# RFG-controller.net
KiCad netlist of a schematic drawn in EAGLE
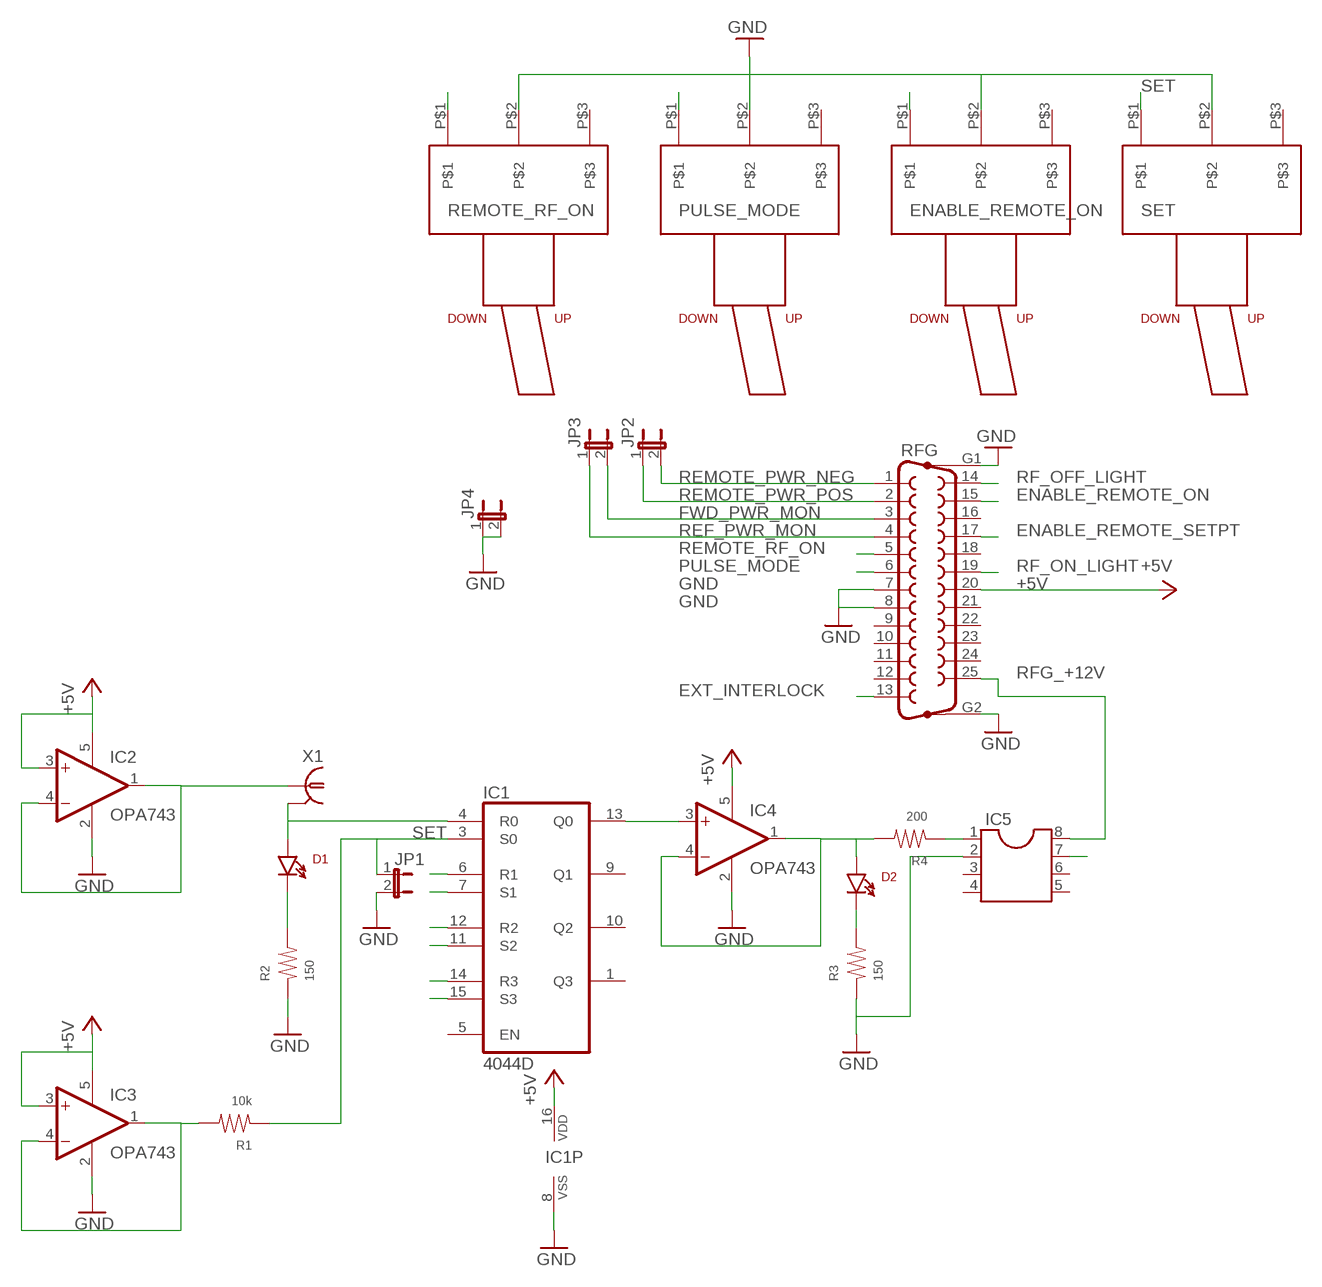
[diagram p0: schematic, sheet 1]

(export (version "E")
  (design (tool "Eeschema 10.0.6"))
  (components
    (comp (ref "D1")
      (value "LED")
      (footprint "eagle-import:LTL-533-11")
      (libsource (lib "eagle-import") (part "LED"))
    )
    (comp (ref "D2")
      (value "LED")
      (footprint "eagle-import:LTL-533-11")
      (libsource (lib "eagle-import") (part "LED"))
    )
    (comp (ref "ENABLE_REMOTE_ON")
      (value "SPDT-TOGGLE")
      (footprint "eagle-import:7101MD9AV2BE")
      (libsource (lib "eagle-import") (part "SPDT-TOGGLE"))
    )
    (comp (ref "IC1")
      (value "4044D")
      (footprint "eagle-import:SO16")
      (libsource (lib "eagle-import") (part "4044D"))
    )
    (comp (ref "IC2")
      (value "OPA743")
      (footprint "eagle-import:SOT23-5")
      (fields (field (name "PARTNO") "OPA743NA/3KCT-ND"))
      (libsource (lib "eagle-import") (part "OPA743"))
    )
    (comp (ref "IC3")
      (value "OPA743")
      (footprint "eagle-import:SOT23-5")
      (fields (field (name "PARTNO") "OPA743NA/3KCT-ND"))
      (libsource (lib "eagle-import") (part "OPA743"))
    )
    (comp (ref "IC4")
      (value "OPA743")
      (footprint "eagle-import:SOT23-5")
      (fields (field (name "PARTNO") "OPA743NA/3KCT-ND"))
      (libsource (lib "eagle-import") (part "OPA743"))
    )
    (comp (ref "IC5")
      (value "DIL8")
      (footprint "eagle-import:DIL08")
      (libsource (lib "eagle-import") (part "DIL8"))
    )
    (comp (ref "JP1")
      (value "JP1E")
      (footprint "eagle-import:JP1")
      (libsource (lib "eagle-import") (part "JP1E"))
    )
    (comp (ref "JP2")
      (value "JP1E")
      (footprint "eagle-import:JP1")
      (libsource (lib "eagle-import") (part "JP1E"))
    )
    (comp (ref "JP3")
      (value "JP1E")
      (footprint "eagle-import:JP1")
      (libsource (lib "eagle-import") (part "JP1E"))
    )
    (comp (ref "JP4")
      (value "JP1E")
      (footprint "eagle-import:JP1")
      (libsource (lib "eagle-import") (part "JP1E"))
    )
    (comp (ref "PULSE_MODE")
      (value "SPDT-TOGGLE")
      (footprint "eagle-import:7101MD9AV2BE")
      (libsource (lib "eagle-import") (part "SPDT-TOGGLE"))
    )
    (comp (ref "R1")
      (value "10k")
      (footprint "eagle-import:0603")
      (libsource (lib "eagle-import") (part "RES0603"))
    )
    (comp (ref "R2")
      (value "150")
      (footprint "eagle-import:0603")
      (libsource (lib "eagle-import") (part "RES0603"))
    )
    (comp (ref "R3")
      (value "150")
      (footprint "eagle-import:0603")
      (libsource (lib "eagle-import") (part "RES0603"))
    )
    (comp (ref "R4")
      (value "200")
      (footprint "eagle-import:0603")
      (libsource (lib "eagle-import") (part "RES0603"))
    )
    (comp (ref "REMOTE_ON")
      (value "SPDT-TOGGLE")
      (footprint "eagle-import:7101MD9AV2BE")
      (libsource (lib "eagle-import") (part "SPDT-TOGGLE"))
    )
    (comp (ref "RFG")
      (value "F25HP")
      (footprint "eagle-import:F25HP")
      (libsource (lib "eagle-import") (part "F25HP"))
    )
    (comp (ref "SET")
      (value "SPDT-TOGGLE")
      (footprint "eagle-import:7101MD9AV2BE")
      (libsource (lib "eagle-import") (part "SPDT-TOGGLE"))
    )
    (comp (ref "X1")
      (value "BNC-H")
      (footprint "eagle-import:BNC90")
      (libsource (lib "eagle-import") (part "BNC-H"))
    )
  )
  (nets
    (net (code "1") (name "+5V") (class "Default")
      (node (ref "IC1") (pin "16") (pinfunction "VDD_16") (pintype "power_in"))
      (node (ref "IC2") (pin "3") (pinfunction "+IN_3") (pintype "input"))
      (node (ref "IC2") (pin "5") (pinfunction "V+_5") (pintype "power_in"))
      (node (ref "IC3") (pin "3") (pinfunction "+IN_3") (pintype "input"))
      (node (ref "IC3") (pin "5") (pinfunction "V+_5") (pintype "power_in"))
      (node (ref "IC4") (pin "5") (pinfunction "V+_5") (pintype "power_in"))
      (node (ref "RFG") (pin "20") (pinfunction "20_20") (pintype "passive"))
    )
    (net (code "2") (name "/ENABLE_REMOTE_ON") (class "Default")
      (node (ref "ENABLE_REMOTE_ON") (pin "P$1") (pinfunction "P$1_P$1") (pintype "bidirectional"))
      (node (ref "RFG") (pin "15") (pinfunction "15_15") (pintype "passive"))
    )
    (net (code "3") (name "/ENABLE_REMOTE_SETPT") (class "Default")
      (node (ref "RFG") (pin "17") (pinfunction "17_17") (pintype "passive"))
    )
    (net (code "4") (name "/EXT_INTERLOCK") (class "Default")
      (node (ref "IC5") (pin "7") (pinfunction "7_7") (pintype "passive"))
      (node (ref "RFG") (pin "13") (pinfunction "13_13") (pintype "passive"))
    )
    (net (code "5") (name "/FWD_PWR_MON") (class "Default")
      (node (ref "JP3") (pin "2") (pinfunction "2_2") (pintype "passive"))
      (node (ref "RFG") (pin "3") (pinfunction "3_3") (pintype "passive"))
    )
    (net (code "6") (name "/PULSE_MODE") (class "Default")
      (node (ref "PULSE_MODE") (pin "P$1") (pinfunction "P$1_P$1") (pintype "bidirectional"))
      (node (ref "RFG") (pin "6") (pinfunction "6_6") (pintype "passive"))
    )
    (net (code "7") (name "/REF_PWR_MON") (class "Default")
      (node (ref "JP3") (pin "1") (pinfunction "1_1") (pintype "passive"))
      (node (ref "RFG") (pin "4") (pinfunction "4_4") (pintype "passive"))
    )
    (net (code "8") (name "/REMOTE_PWR_NEG") (class "Default")
      (node (ref "JP2") (pin "2") (pinfunction "2_2") (pintype "passive"))
      (node (ref "RFG") (pin "1") (pinfunction "1_1") (pintype "passive"))
    )
    (net (code "9") (name "/REMOTE_PWR_POS") (class "Default")
      (node (ref "JP2") (pin "1") (pinfunction "1_1") (pintype "passive"))
      (node (ref "RFG") (pin "2") (pinfunction "2_2") (pintype "passive"))
    )
    (net (code "10") (name "/REMOTE_RF_ON") (class "Default")
      (node (ref "REMOTE_ON") (pin "P$1") (pinfunction "P$1_P$1") (pintype "bidirectional"))
      (node (ref "RFG") (pin "5") (pinfunction "5_5") (pintype "passive"))
    )
    (net (code "11") (name "/RFG_+12V") (class "Default")
      (node (ref "IC5") (pin "8") (pinfunction "8_8") (pintype "passive"))
      (node (ref "RFG") (pin "25") (pinfunction "25_25") (pintype "passive"))
    )
    (net (code "12") (name "/RF_OFF_LIGHT") (class "Default")
      (node (ref "RFG") (pin "14") (pinfunction "14_14") (pintype "passive"))
    )
    (net (code "13") (name "/RF_ON_LIGHT") (class "Default")
      (node (ref "RFG") (pin "19") (pinfunction "19_19") (pintype "passive"))
    )
    (net (code "14") (name "/SET") (class "Default")
      (node (ref "IC1") (pin "3") (pinfunction "S0_3") (pintype "input"))
      (node (ref "JP1") (pin "1") (pinfunction "1_1") (pintype "passive"))
      (node (ref "R1") (pin "1") (pinfunction "P$1_1") (pintype "passive"))
      (node (ref "SET") (pin "P$1") (pinfunction "P$1_P$1") (pintype "bidirectional"))
    )
    (net (code "15") (name "GND") (class "Default")
      (node (ref "ENABLE_REMOTE_ON") (pin "P$2") (pinfunction "P$2_P$2") (pintype "bidirectional"))
      (node (ref "IC1") (pin "11") (pinfunction "S2_11") (pintype "input"))
      (node (ref "IC1") (pin "12") (pinfunction "R2_12") (pintype "input"))
      (node (ref "IC1") (pin "14") (pinfunction "R3_14") (pintype "input"))
      (node (ref "IC1") (pin "15") (pinfunction "S3_15") (pintype "input"))
      (node (ref "IC1") (pin "6") (pinfunction "R1_6") (pintype "input"))
      (node (ref "IC1") (pin "7") (pinfunction "S1_7") (pintype "input"))
      (node (ref "IC1") (pin "8") (pinfunction "VSS_8") (pintype "power_in"))
      (node (ref "IC2") (pin "2") (pinfunction "V-_2") (pintype "power_in"))
      (node (ref "IC3") (pin "2") (pinfunction "V-_2") (pintype "power_in"))
      (node (ref "IC4") (pin "2") (pinfunction "V-_2") (pintype "power_in"))
      (node (ref "IC5") (pin "2") (pinfunction "2_2") (pintype "passive"))
      (node (ref "JP1") (pin "2") (pinfunction "2_2") (pintype "passive"))
      (node (ref "JP4") (pin "1") (pinfunction "1_1") (pintype "passive"))
      (node (ref "JP4") (pin "2") (pinfunction "2_2") (pintype "passive"))
      (node (ref "PULSE_MODE") (pin "P$2") (pinfunction "P$2_P$2") (pintype "bidirectional"))
      (node (ref "R2") (pin "1") (pinfunction "P$1_1") (pintype "passive"))
      (node (ref "R3") (pin "1") (pinfunction "P$1_1") (pintype "passive"))
      (node (ref "REMOTE_ON") (pin "P$2") (pinfunction "P$2_P$2") (pintype "bidirectional"))
      (node (ref "RFG") (pin "7") (pinfunction "7_7") (pintype "passive"))
      (node (ref "RFG") (pin "8") (pinfunction "8_8") (pintype "passive"))
      (node (ref "RFG") (pin "G1") (pinfunction "G1_G1") (pintype "passive"))
      (node (ref "RFG") (pin "G2") (pinfunction "G2_G2") (pintype "passive"))
      (node (ref "SET") (pin "P$2") (pinfunction "P$2_P$2") (pintype "bidirectional"))
    )
    (net (code "16") (name "Net-(IC1A-Q0)") (class "Default")
      (node (ref "IC1") (pin "13") (pinfunction "Q0_13") (pintype "output"))
      (node (ref "IC4") (pin "3") (pinfunction "+IN_3") (pintype "input"))
    )
    (net (code "17") (name "Net-(IC1A-R0)") (class "Default")
      (node (ref "D1") (pin "A") (pinfunction "A_A") (pintype "bidirectional"))
      (node (ref "IC1") (pin "4") (pinfunction "R0_4") (pintype "input"))
      (node (ref "X1") (pin "2") (pinfunction "2_2") (pintype "passive"))
    )
    (net (code "18") (name "Net-(IC2--IN)") (class "Default")
      (node (ref "IC2") (pin "1") (pinfunction "OUT_1") (pintype "output"))
      (node (ref "IC2") (pin "4") (pinfunction "-IN_4") (pintype "input"))
      (node (ref "X1") (pin "1") (pinfunction "1_1") (pintype "passive"))
    )
    (net (code "19") (name "Net-(IC3--IN)") (class "Default")
      (node (ref "IC3") (pin "1") (pinfunction "OUT_1") (pintype "output"))
      (node (ref "IC3") (pin "4") (pinfunction "-IN_4") (pintype "input"))
      (node (ref "R1") (pin "2") (pinfunction "P$2_2") (pintype "passive"))
    )
    (net (code "20") (name "Net-(IC4--IN)") (class "Default")
      (node (ref "D2") (pin "A") (pinfunction "A_A") (pintype "bidirectional"))
      (node (ref "IC4") (pin "1") (pinfunction "OUT_1") (pintype "output"))
      (node (ref "IC4") (pin "4") (pinfunction "-IN_4") (pintype "input"))
      (node (ref "R4") (pin "2") (pinfunction "P$2_2") (pintype "passive"))
    )
    (net (code "21") (name "Net-(R2-P$2)") (class "Default")
      (node (ref "D1") (pin "C") (pinfunction "C_C") (pintype "bidirectional"))
      (node (ref "R2") (pin "2") (pinfunction "P$2_2") (pintype "passive"))
    )
    (net (code "22") (name "Net-(R3-P$2)") (class "Default")
      (node (ref "D2") (pin "C") (pinfunction "C_C") (pintype "bidirectional"))
      (node (ref "R3") (pin "2") (pinfunction "P$2_2") (pintype "passive"))
    )
    (net (code "23") (name "Net-(R4-P$1)") (class "Default")
      (node (ref "IC5") (pin "1") (pinfunction "1_1") (pintype "passive"))
      (node (ref "R4") (pin "1") (pinfunction "P$1_1") (pintype "passive"))
    )
    (net (code "24") (name "unconnected-(ENABLE_REMOTE_ON-PadP$3)") (class "Default")
      (node (ref "ENABLE_REMOTE_ON") (pin "P$3") (pinfunction "P$3_P$3") (pintype "bidirectional"))
    )
    (net (code "25") (name "unconnected-(IC1A-EN-Pad5)") (class "Default")
      (node (ref "IC1") (pin "5") (pinfunction "EN_5") (pintype "input"))
    )
    (net (code "26") (name "unconnected-(IC1A-Q1-Pad9)") (class "Default")
      (node (ref "IC1") (pin "9") (pinfunction "Q1_9") (pintype "output"))
    )
    (net (code "27") (name "unconnected-(IC1A-Q2-Pad10)") (class "Default")
      (node (ref "IC1") (pin "10") (pinfunction "Q2_10") (pintype "output"))
    )
    (net (code "28") (name "unconnected-(IC1A-Q3-Pad1)") (class "Default")
      (node (ref "IC1") (pin "1") (pinfunction "Q3_1") (pintype "output"))
    )
    (net (code "29") (name "unconnected-(IC5-Pad3)") (class "Default")
      (node (ref "IC5") (pin "3") (pinfunction "3_3") (pintype "passive"))
    )
    (net (code "30") (name "unconnected-(IC5-Pad4)") (class "Default")
      (node (ref "IC5") (pin "4") (pinfunction "4_4") (pintype "passive"))
    )
    (net (code "31") (name "unconnected-(IC5-Pad5)") (class "Default")
      (node (ref "IC5") (pin "5") (pinfunction "5_5") (pintype "passive"))
    )
    (net (code "32") (name "unconnected-(IC5-Pad6)") (class "Default")
      (node (ref "IC5") (pin "6") (pinfunction "6_6") (pintype "passive"))
    )
    (net (code "33") (name "unconnected-(PULSE_MODE-PadP$3)") (class "Default")
      (node (ref "PULSE_MODE") (pin "P$3") (pinfunction "P$3_P$3") (pintype "bidirectional"))
    )
    (net (code "34") (name "unconnected-(REMOTE_ON-PadP$3)") (class "Default")
      (node (ref "REMOTE_ON") (pin "P$3") (pinfunction "P$3_P$3") (pintype "bidirectional"))
    )
    (net (code "35") (name "unconnected-(RFG-Pad9)") (class "Default")
      (node (ref "RFG") (pin "9") (pinfunction "9_9") (pintype "passive"))
    )
    (net (code "36") (name "unconnected-(RFG-Pad10)") (class "Default")
      (node (ref "RFG") (pin "10") (pinfunction "10_10") (pintype "passive"))
    )
    (net (code "37") (name "unconnected-(RFG-Pad11)") (class "Default")
      (node (ref "RFG") (pin "11") (pinfunction "11_11") (pintype "passive"))
    )
    (net (code "38") (name "unconnected-(RFG-Pad12)") (class "Default")
      (node (ref "RFG") (pin "12") (pinfunction "12_12") (pintype "passive"))
    )
    (net (code "39") (name "unconnected-(RFG-Pad16)") (class "Default")
      (node (ref "RFG") (pin "16") (pinfunction "16_16") (pintype "passive"))
    )
    (net (code "40") (name "unconnected-(RFG-Pad18)") (class "Default")
      (node (ref "RFG") (pin "18") (pinfunction "18_18") (pintype "passive"))
    )
    (net (code "41") (name "unconnected-(RFG-Pad21)") (class "Default")
      (node (ref "RFG") (pin "21") (pinfunction "21_21") (pintype "passive"))
    )
    (net (code "42") (name "unconnected-(RFG-Pad22)") (class "Default")
      (node (ref "RFG") (pin "22") (pinfunction "22_22") (pintype "passive"))
    )
    (net (code "43") (name "unconnected-(RFG-Pad23)") (class "Default")
      (node (ref "RFG") (pin "23") (pinfunction "23_23") (pintype "passive"))
    )
    (net (code "44") (name "unconnected-(RFG-Pad24)") (class "Default")
      (node (ref "RFG") (pin "24") (pinfunction "24_24") (pintype "passive"))
    )
    (net (code "45") (name "unconnected-(SET-PadP$3)") (class "Default")
      (node (ref "SET") (pin "P$3") (pinfunction "P$3_P$3") (pintype "bidirectional"))
    )
  )
)
